# Actuation.net
KiCad netlist of a schematic drawn in Altium Designer
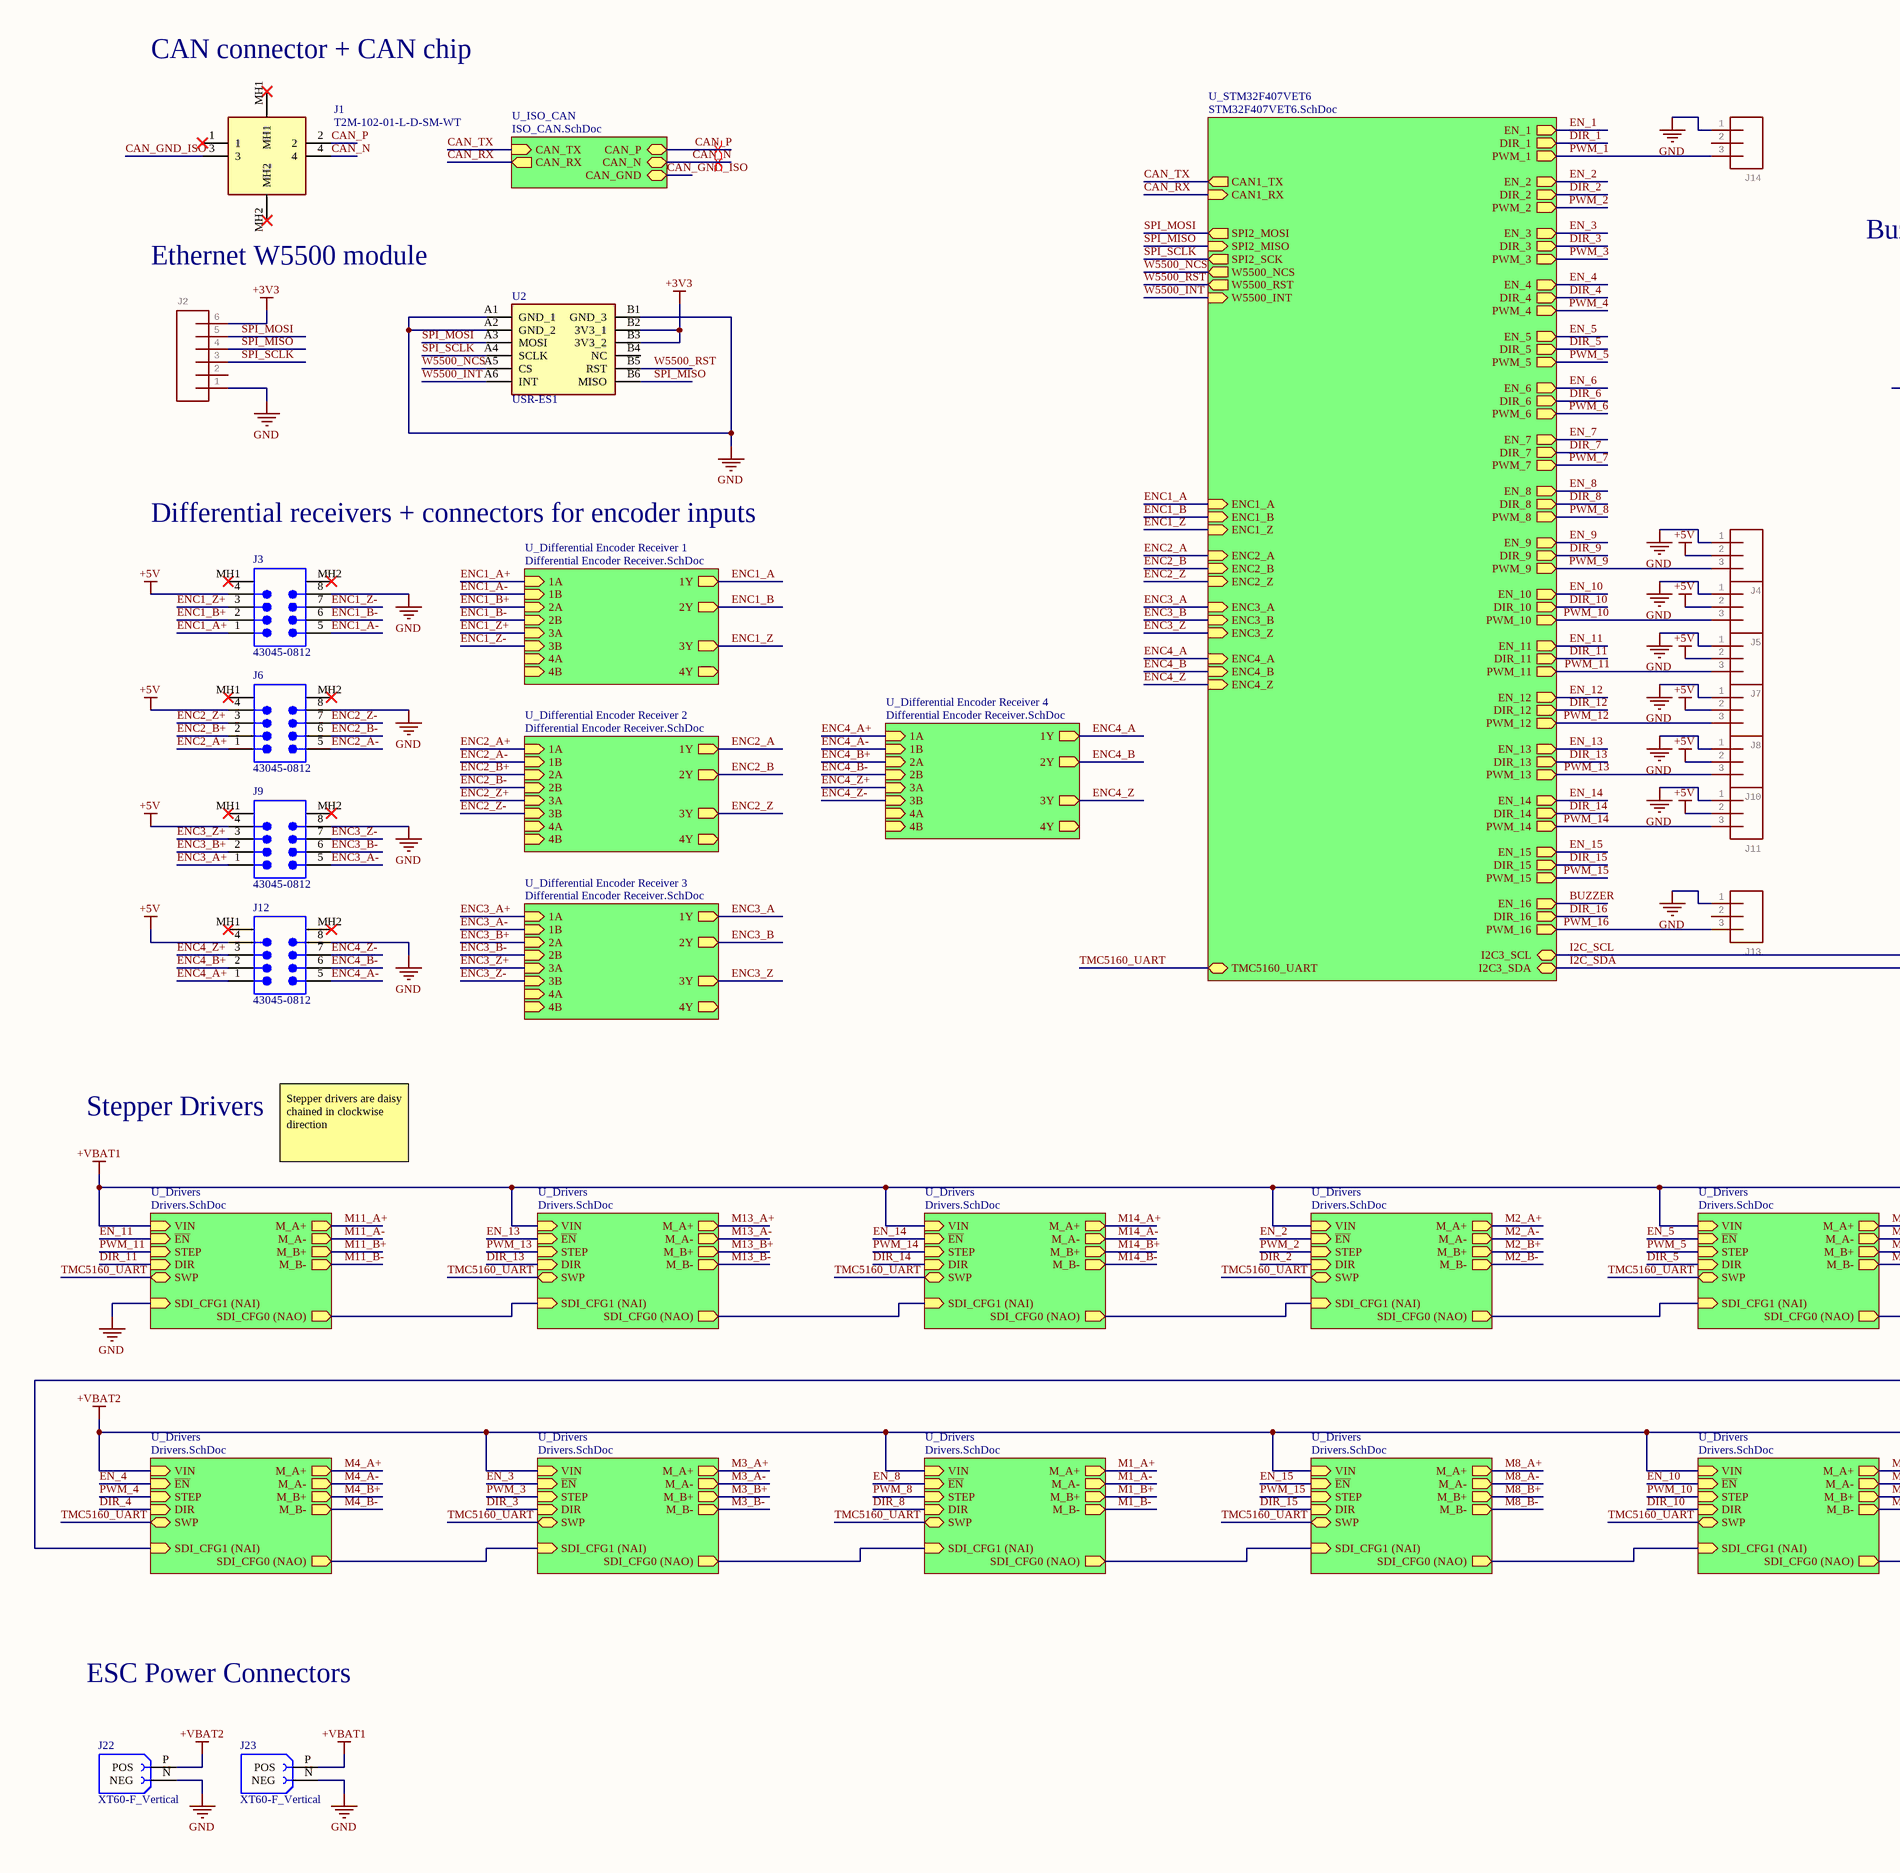
[diagram p0: Actuation.SchDoc, left]
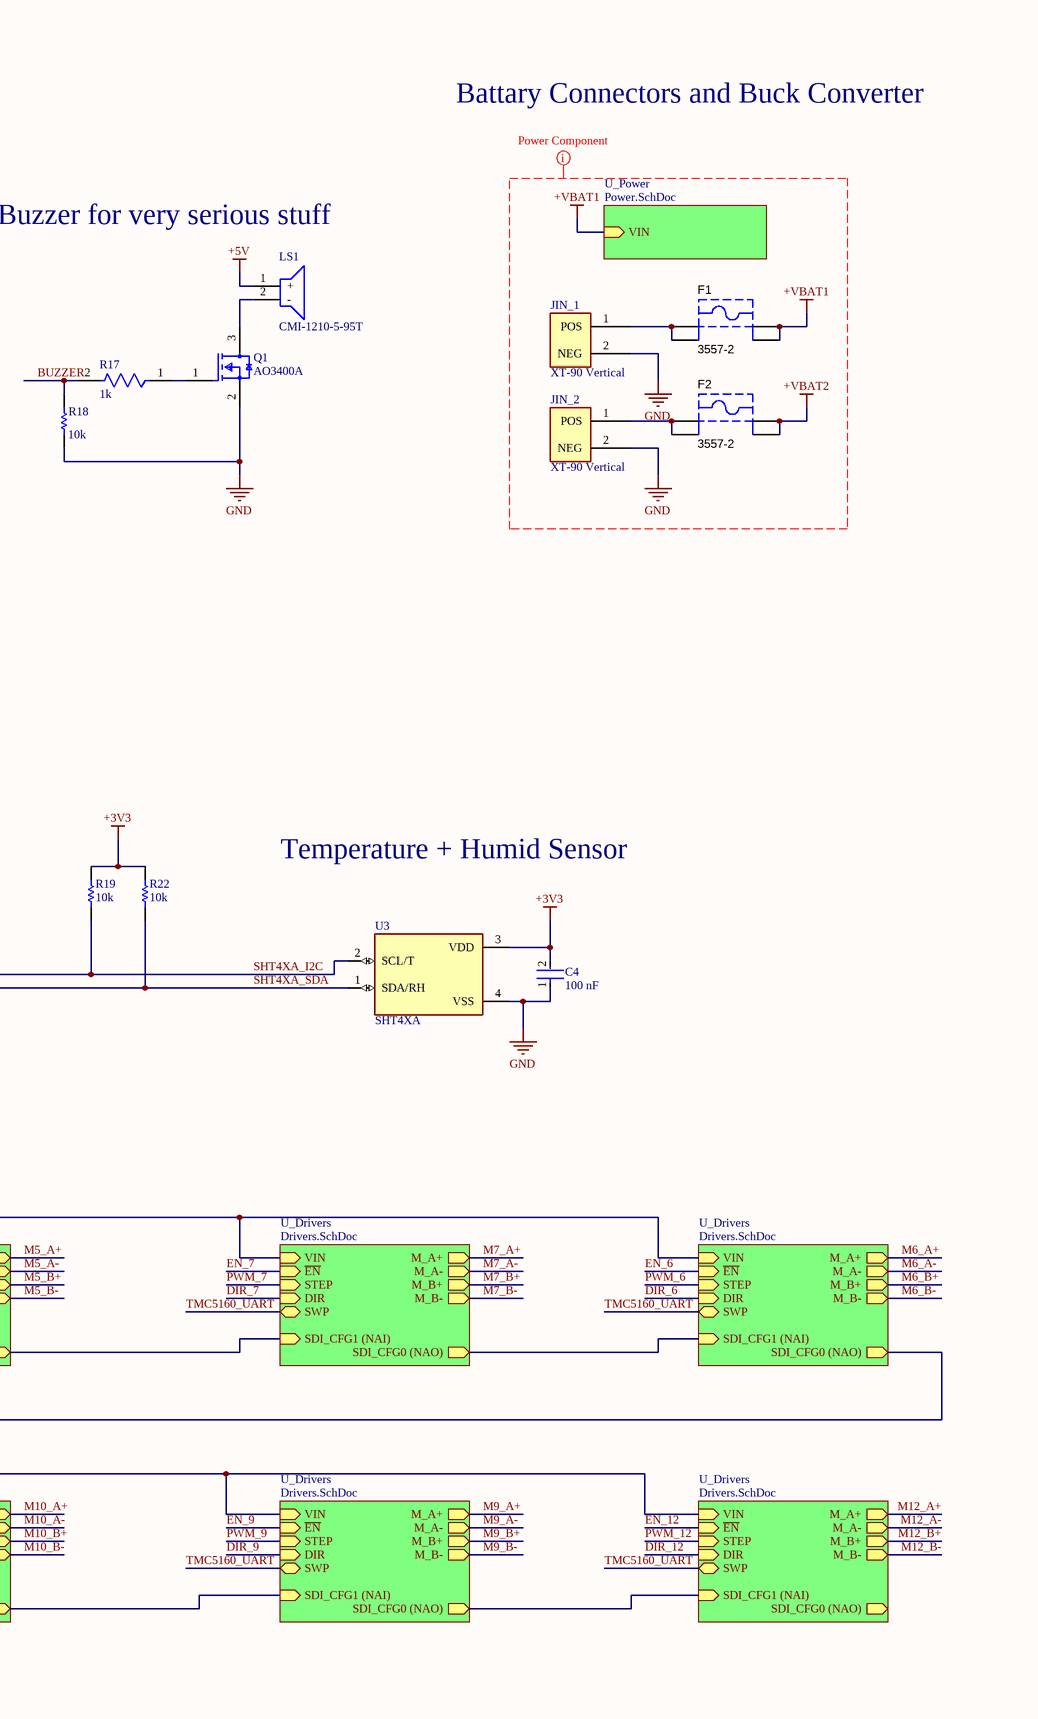
[diagram p1: Actuation.SchDoc, right]

(export (version "E")
  (design (tool "Eeschema 10.0.6"))
  (components
    (comp (ref "C4")
      (value "CC0603KRX7R9BB104")
      (footprint "FP-CC0603-DA-MFG")
      (description "CAP CER 0.1UF 50V X7R 0603")
      (fields
        (field (name "MANUFACTURER") "YAGEO")
        (field (name "VOLTAGE") "50 V")
        (field (name "CAPACITANCE") "100 nF")
      )
      (libsource (lib "Altium Content Vault") (part "11868f565c42a9108669ba33697ecf6"))
    )
    (comp (ref "F1")
      (value "3557-2")
      (footprint "KSTN-3557-2")
      (description "FUSE HOLDER, PCB MOUNT, 500VAC, 20A, ROHS")
      (fields (field (name "VOLTAGE") "500V") (field (name "MANUFACTURER") "Keystone-Electronics"))
      (libsource (lib "Altium Content Vault") (part "FUSE_HOLDER-4"))
    )
    (comp (ref "F2")
      (value "3557-2")
      (footprint "KSTN-3557-2")
      (description "FUSE HOLDER, PCB MOUNT, 500VAC, 20A, ROHS")
      (fields (field (name "VOLTAGE") "500V") (field (name "MANUFACTURER") "Keystone-Electronics"))
      (libsource (lib "Altium Content Vault") (part "FUSE_HOLDER-4"))
    )
    (comp (ref "J1")
      (value "T2M-102-01-L-D-SM-WT")
      (footprint "T2M10201LDSMWT")
      (description "Connector")
      (fields (field (name "MOUSER PART NUMBER") "200-T2M10201LDSMWT"))
      (libsource (lib "BumbleBee Autonomous Systems - NUS") (part "T2M-102-01-L-D-SM-WT"))
    )
    (comp (ref "J2")
      (value "Multi connection point. Often used as Generic Header-pin footprint for 0.1 inch spaced/style header connections    On any of the 0.1 inch spaced packages, you can populate with these:  Break Away Headers - Straight (PRT-00116)   Break Away Male Headers - Right Angle (PRT-00553)   Female Headers (PRT-00115)   Break Away Headers - Machine Pin (PRT-00117)   Break Away Female Headers - Swiss Machine Pin (PRT-00743)   Arduino Stackable Header - 6 Pin (PRT-09280)   Screw Terminals 2.54mm Pitch (6-Pin) (PRT-16499)        For SCREWTERMINALS and SPRING TERMINALS visit here:  Screw Terimnals on SparkFun.com (5mm/3.5mm/2.54mm spacing)       This device is also useful as a general connection point to wire up your design to another part of your project. Our various solder wires solder well into these plated through hole pads.  Hook-Up Wire - Assortment (Stranded, 22 AWG) (PRT-11375)   Hook-Up Wire - Assortment (Solid Core, 22 AWG) (PRT-11367)   View the entire wire category on our website here")
      (footprint "1X06_LOCK")
      (libsource (lib "SparkFun-Connectors.Library") (part "CONN_06LOCK"))
    )
    (comp (ref "J3")
      (value "43045-0812")
      (footprint "MOLX-43045-0812_V")
      (libsource (lib "Altium Content Vault") (part "MOLX-43045-0812"))
    )
    (comp (ref "J4")
      (value "Multi connection point. Often used as Generic Header-pin footprint for 0.1 inch spaced/style header connections    On any of the 0.1 inch spaced packages, you can populate with these:  Break Away Headers - Straight (PRT-00116)   Break Away Male Headers - Right Angle (PRT-00553)   Female Headers (PRT-00115)   Break Away Headers - Machine Pin (PRT-00117)   Break Away Female Headers - Swiss Machine Pin (PRT-00743)   Stackable Header - 3 Pin (Female, 0.1\") (PRT-13875)        For SCREWTERMINALS and SPRING TERMINALS visit here:  Screw Terimnals on SparkFun.com (5mm/3.5mm/2.54mm spacing)       This device is also useful as a general connection point to wire up your design to another part of your project. Our various solder wires solder well into these plated through hole pads.  Hook-Up Wire - Assortment (Stranded, 22 AWG) (PRT-11375)   Hook-Up Wire - Assortment (Solid Core, 22 AWG) (PRT-11367)   View the entire wire category on our website here          Special notes:         Molex polarized connector foot print use with SKU : PRT-08232 with associated crimp pins and housings.")
      (footprint "1X03_LOCK")
      (libsource (lib "SparkFun-Connectors.Library") (part "CONN_03LOCK"))
    )
    (comp (ref "J5")
      (value "Multi connection point. Often used as Generic Header-pin footprint for 0.1 inch spaced/style header connections    On any of the 0.1 inch spaced packages, you can populate with these:  Break Away Headers - Straight (PRT-00116)   Break Away Male Headers - Right Angle (PRT-00553)   Female Headers (PRT-00115)   Break Away Headers - Machine Pin (PRT-00117)   Break Away Female Headers - Swiss Machine Pin (PRT-00743)   Stackable Header - 3 Pin (Female, 0.1\") (PRT-13875)        For SCREWTERMINALS and SPRING TERMINALS visit here:  Screw Terimnals on SparkFun.com (5mm/3.5mm/2.54mm spacing)       This device is also useful as a general connection point to wire up your design to another part of your project. Our various solder wires solder well into these plated through hole pads.  Hook-Up Wire - Assortment (Stranded, 22 AWG) (PRT-11375)   Hook-Up Wire - Assortment (Solid Core, 22 AWG) (PRT-11367)   View the entire wire category on our website here          Special notes:         Molex polarized connector foot print use with SKU : PRT-08232 with associated crimp pins and housings.")
      (footprint "1X03_LOCK")
      (libsource (lib "SparkFun-Connectors.Library") (part "CONN_03LOCK"))
    )
    (comp (ref "J6")
      (value "43045-0812")
      (footprint "MOLX-43045-0812_V")
      (libsource (lib "Altium Content Vault") (part "MOLX-43045-0812"))
    )
    (comp (ref "J7")
      (value "Multi connection point. Often used as Generic Header-pin footprint for 0.1 inch spaced/style header connections    On any of the 0.1 inch spaced packages, you can populate with these:  Break Away Headers - Straight (PRT-00116)   Break Away Male Headers - Right Angle (PRT-00553)   Female Headers (PRT-00115)   Break Away Headers - Machine Pin (PRT-00117)   Break Away Female Headers - Swiss Machine Pin (PRT-00743)   Stackable Header - 3 Pin (Female, 0.1\") (PRT-13875)        For SCREWTERMINALS and SPRING TERMINALS visit here:  Screw Terimnals on SparkFun.com (5mm/3.5mm/2.54mm spacing)       This device is also useful as a general connection point to wire up your design to another part of your project. Our various solder wires solder well into these plated through hole pads.  Hook-Up Wire - Assortment (Stranded, 22 AWG) (PRT-11375)   Hook-Up Wire - Assortment (Solid Core, 22 AWG) (PRT-11367)   View the entire wire category on our website here          Special notes:         Molex polarized connector foot print use with SKU : PRT-08232 with associated crimp pins and housings.")
      (footprint "1X03_LOCK")
      (libsource (lib "SparkFun-Connectors.Library") (part "CONN_03LOCK"))
    )
    (comp (ref "J8")
      (value "Multi connection point. Often used as Generic Header-pin footprint for 0.1 inch spaced/style header connections    On any of the 0.1 inch spaced packages, you can populate with these:  Break Away Headers - Straight (PRT-00116)   Break Away Male Headers - Right Angle (PRT-00553)   Female Headers (PRT-00115)   Break Away Headers - Machine Pin (PRT-00117)   Break Away Female Headers - Swiss Machine Pin (PRT-00743)   Stackable Header - 3 Pin (Female, 0.1\") (PRT-13875)        For SCREWTERMINALS and SPRING TERMINALS visit here:  Screw Terimnals on SparkFun.com (5mm/3.5mm/2.54mm spacing)       This device is also useful as a general connection point to wire up your design to another part of your project. Our various solder wires solder well into these plated through hole pads.  Hook-Up Wire - Assortment (Stranded, 22 AWG) (PRT-11375)   Hook-Up Wire - Assortment (Solid Core, 22 AWG) (PRT-11367)   View the entire wire category on our website here          Special notes:         Molex polarized connector foot print use with SKU : PRT-08232 with associated crimp pins and housings.")
      (footprint "1X03_LOCK")
      (libsource (lib "SparkFun-Connectors.Library") (part "CONN_03LOCK"))
    )
    (comp (ref "J9")
      (value "43045-0812")
      (footprint "MOLX-43045-0812_V")
      (libsource (lib "Altium Content Vault") (part "MOLX-43045-0812"))
    )
    (comp (ref "J10")
      (value "Multi connection point. Often used as Generic Header-pin footprint for 0.1 inch spaced/style header connections    On any of the 0.1 inch spaced packages, you can populate with these:  Break Away Headers - Straight (PRT-00116)   Break Away Male Headers - Right Angle (PRT-00553)   Female Headers (PRT-00115)   Break Away Headers - Machine Pin (PRT-00117)   Break Away Female Headers - Swiss Machine Pin (PRT-00743)   Stackable Header - 3 Pin (Female, 0.1\") (PRT-13875)        For SCREWTERMINALS and SPRING TERMINALS visit here:  Screw Terimnals on SparkFun.com (5mm/3.5mm/2.54mm spacing)       This device is also useful as a general connection point to wire up your design to another part of your project. Our various solder wires solder well into these plated through hole pads.  Hook-Up Wire - Assortment (Stranded, 22 AWG) (PRT-11375)   Hook-Up Wire - Assortment (Solid Core, 22 AWG) (PRT-11367)   View the entire wire category on our website here          Special notes:         Molex polarized connector foot print use with SKU : PRT-08232 with associated crimp pins and housings.")
      (footprint "1X03_LOCK")
      (libsource (lib "SparkFun-Connectors.Library") (part "CONN_03LOCK"))
    )
    (comp (ref "J11")
      (value "Multi connection point. Often used as Generic Header-pin footprint for 0.1 inch spaced/style header connections    On any of the 0.1 inch spaced packages, you can populate with these:  Break Away Headers - Straight (PRT-00116)   Break Away Male Headers - Right Angle (PRT-00553)   Female Headers (PRT-00115)   Break Away Headers - Machine Pin (PRT-00117)   Break Away Female Headers - Swiss Machine Pin (PRT-00743)   Stackable Header - 3 Pin (Female, 0.1\") (PRT-13875)        For SCREWTERMINALS and SPRING TERMINALS visit here:  Screw Terimnals on SparkFun.com (5mm/3.5mm/2.54mm spacing)       This device is also useful as a general connection point to wire up your design to another part of your project. Our various solder wires solder well into these plated through hole pads.  Hook-Up Wire - Assortment (Stranded, 22 AWG) (PRT-11375)   Hook-Up Wire - Assortment (Solid Core, 22 AWG) (PRT-11367)   View the entire wire category on our website here          Special notes:         Molex polarized connector foot print use with SKU : PRT-08232 with associated crimp pins and housings.")
      (footprint "1X03_LOCK")
      (libsource (lib "SparkFun-Connectors.Library") (part "CONN_03LOCK"))
    )
    (comp (ref "J12")
      (value "43045-0812")
      (footprint "MOLX-43045-0812_V")
      (libsource (lib "Altium Content Vault") (part "MOLX-43045-0812"))
    )
    (comp (ref "J13")
      (value "Multi connection point. Often used as Generic Header-pin footprint for 0.1 inch spaced/style header connections    On any of the 0.1 inch spaced packages, you can populate with these:  Break Away Headers - Straight (PRT-00116)   Break Away Male Headers - Right Angle (PRT-00553)   Female Headers (PRT-00115)   Break Away Headers - Machine Pin (PRT-00117)   Break Away Female Headers - Swiss Machine Pin (PRT-00743)   Stackable Header - 3 Pin (Female, 0.1\") (PRT-13875)        For SCREWTERMINALS and SPRING TERMINALS visit here:  Screw Terimnals on SparkFun.com (5mm/3.5mm/2.54mm spacing)       This device is also useful as a general connection point to wire up your design to another part of your project. Our various solder wires solder well into these plated through hole pads.  Hook-Up Wire - Assortment (Stranded, 22 AWG) (PRT-11375)   Hook-Up Wire - Assortment (Solid Core, 22 AWG) (PRT-11367)   View the entire wire category on our website here          Special notes:         Molex polarized connector foot print use with SKU : PRT-08232 with associated crimp pins and housings.")
      (footprint "1X03_LOCK")
      (libsource (lib "SparkFun-Connectors.Library") (part "CONN_03LOCK"))
    )
    (comp (ref "J14")
      (value "Multi connection point. Often used as Generic Header-pin footprint for 0.1 inch spaced/style header connections    On any of the 0.1 inch spaced packages, you can populate with these:  Break Away Headers - Straight (PRT-00116)   Break Away Male Headers - Right Angle (PRT-00553)   Female Headers (PRT-00115)   Break Away Headers - Machine Pin (PRT-00117)   Break Away Female Headers - Swiss Machine Pin (PRT-00743)   Stackable Header - 3 Pin (Female, 0.1\") (PRT-13875)        For SCREWTERMINALS and SPRING TERMINALS visit here:  Screw Terimnals on SparkFun.com (5mm/3.5mm/2.54mm spacing)       This device is also useful as a general connection point to wire up your design to another part of your project. Our various solder wires solder well into these plated through hole pads.  Hook-Up Wire - Assortment (Stranded, 22 AWG) (PRT-11375)   Hook-Up Wire - Assortment (Solid Core, 22 AWG) (PRT-11367)   View the entire wire category on our website here          Special notes:         Molex polarized connector foot print use with SKU : PRT-08232 with associated crimp pins and housings.")
      (footprint "1X03_LOCK")
      (libsource (lib "SparkFun-Connectors.Library") (part "CONN_03LOCK"))
    )
    (comp (ref "J22")
      (value "XT60-F_Vertical")
      (footprint "AMASS_XT60-F_1x02_P7.20mm_Vertical")
      (libsource (lib "BumbleBee Autonomous Systems - NUS") (part "XT90PW-F"))
    )
    (comp (ref "J23")
      (value "XT60-F_Vertical")
      (footprint "AMASS_XT60-F_1x02_P7.20mm_Vertical")
      (libsource (lib "BumbleBee Autonomous Systems - NUS") (part "XT90PW-F"))
    )
    (comp (ref "JIN_1")
      (value "XT-90 Vertical")
      (footprint "XT-90 Vertical-Footprint-1")
      (libsource (lib "BumbleBee Autonomous Systems - NUS") (part "XT90 Vertical"))
    )
    (comp (ref "JIN_2")
      (value "XT-90 Vertical")
      (footprint "XT-90 Vertical-Footprint-1")
      (libsource (lib "BumbleBee Autonomous Systems - NUS") (part "XT90 Vertical"))
    )
    (comp (ref "LS1")
      (value "CMI-1210-5-95T")
      (footprint "SamacSys:CMI1210595T")
      (description "Loudspeaker or Buzzer")
      (fields (field (name "MOUSER PART NUMBER") "179-CMI-1210-5-95T"))
      (libsource (lib "*") (part "CMI-1210-5-95T"))
    )
    (comp (ref "Q1")
      (value "AO3400A")
      (footprint "FP-SOT23-MFG")
      (description "MOSFET N-CH 30V 5.7A SOT23")
      (libsource (lib "Altium Content Vault") (part "0a9ea7c96deaaede766a5b531c28de0"))
    )
    (comp (ref "R17")
      (value "1k")
      (footprint "FP-RC0603-0_55-IPC_C")
      (description "RC0603FR-071KL. RES 1K OHM 1% 1/10W 0603")
      (fields (field (name "TOLERANCE") "1%"))
      (libsource (lib "Altium Content Vault") (part "1029c3af85768c4190bb7ad29bc67b5"))
    )
    (comp (ref "R18")
      (value "0603WAF1002T5E")
      (footprint "RESC1609X50X30NL8T20")
      (description "100mW Thick Film Resistors 75V ±100ppm/℃ ±1% 10kΩ 0603 Chip Resistor - Surface Mount ROHS")
      (fields (field (name "RESISTANCE") "10k"))
      (libsource (lib "Altium Content Vault") (part "RES-2"))
    )
    (comp (ref "R19")
      (value "0603WAF1002T5E")
      (footprint "RESC1609X50X30NL8T20")
      (description "100mW Thick Film Resistors 75V ±100ppm/℃ ±1% 10kΩ 0603 Chip Resistor - Surface Mount ROHS")
      (fields (field (name "RESISTANCE") "10k"))
      (libsource (lib "Altium Content Vault") (part "RES-2"))
    )
    (comp (ref "R22")
      (value "0603WAF1002T5E")
      (footprint "RESC1609X50X30NL8T20")
      (description "100mW Thick Film Resistors 75V ±100ppm/℃ ±1% 10kΩ 0603 Chip Resistor - Surface Mount ROHS")
      (fields (field (name "RESISTANCE") "10k"))
      (libsource (lib "Altium Content Vault") (part "RES-2"))
    )
    (comp (ref "U2")
      (value "USR-ES1")
      (footprint "USRES1")
      (description "Integrated Circuit")
      (libsource (lib "BumbleBee Autonomous Systems - NUS") (part "USR-ES1"))
    )
    (comp (ref "U3")
      (value "SHT4XA")
      (footprint "SHT4XA")
      (description "Automotive Grade Relative Humidity Temperature Sensor, Â±3 %RH, Â±0.3 Â°C")
      (fields (field (name "MF") "Sensirion") (field (name "MP") "SHT40A-AD1B-R3"))
      (libsource (lib "BumbleBee Autonomous Systems - NUS") (part "SHT4XA"))
    )
  )
  (nets
    (net (code "1") (name "+3V3") (class "Default")
      (node (ref "C4") (pin "2") (pinfunction "2_2") (pintype "passive"))
      (node (ref "J2") (pin "6") (pinfunction "6_6") (pintype "passive"))
      (node (ref "R19") (pin "2") (pinfunction "2_2") (pintype "passive"))
      (node (ref "R22") (pin "2") (pinfunction "2_2") (pintype "passive"))
      (node (ref "U2") (pin "B2") (pinfunction "3V3_1_B2") (pintype "passive"))
      (node (ref "U2") (pin "B3") (pinfunction "3V3_2_B3") (pintype "passive"))
      (node (ref "U3") (pin "3") (pinfunction "VDD_3") (pintype "power_in"))
    )
    (net (code "2") (name "+5V") (class "Default")
      (node (ref "J10") (pin "2") (pinfunction "2_2") (pintype "passive"))
      (node (ref "J11") (pin "2") (pinfunction "2_2") (pintype "passive"))
      (node (ref "J12") (pin "4") (pinfunction "4_4") (pintype "passive"))
      (node (ref "J3") (pin "4") (pinfunction "4_4") (pintype "passive"))
      (node (ref "J4") (pin "2") (pinfunction "2_2") (pintype "passive"))
      (node (ref "J5") (pin "2") (pinfunction "2_2") (pintype "passive"))
      (node (ref "J6") (pin "4") (pinfunction "4_4") (pintype "passive"))
      (node (ref "J7") (pin "2") (pinfunction "2_2") (pintype "passive"))
      (node (ref "J8") (pin "2") (pinfunction "2_2") (pintype "passive"))
      (node (ref "J9") (pin "4") (pinfunction "4_4") (pintype "passive"))
      (node (ref "LS1") (pin "1") (pinfunction "+_1") (pintype "passive"))
    )
    (net (code "3") (name "+VBAT1") (class "Default")
      (node (ref "F1") (pin "3") (pinfunction "3_3") (pintype "passive"))
      (node (ref "F1") (pin "4") (pinfunction "4_4") (pintype "passive"))
      (node (ref "J23") (pin "P") (pinfunction "POS_P") (pintype "passive"))
    )
    (net (code "4") (name "+VBAT2") (class "Default")
      (node (ref "F2") (pin "3") (pinfunction "3_3") (pintype "passive"))
      (node (ref "F2") (pin "4") (pinfunction "4_4") (pintype "passive"))
      (node (ref "J22") (pin "P") (pinfunction "POS_P") (pintype "passive"))
    )
    (net (code "17") (name "/BUZZER") (class "Default")
      (node (ref "R17") (pin "2") (pinfunction "2_2") (pintype "passive"))
      (node (ref "R18") (pin "1") (pinfunction "1_1") (pintype "passive"))
    )
    (net (code "18") (name "/CAN_GND_ISO") (class "Default")
      (node (ref "J1") (pin "3") (pinfunction "3_3") (pintype "passive"))
    )
    (net (code "19") (name "/CAN_N") (class "Default")
      (node (ref "J1") (pin "4") (pinfunction "4_4") (pintype "passive"))
    )
    (net (code "20") (name "/CAN_P") (class "Default")
      (node (ref "J1") (pin "2") (pinfunction "2_2") (pintype "passive"))
    )
    (net (code "40") (name "/ENC1_A+") (class "Default")
      (node (ref "J3") (pin "1") (pinfunction "1_1") (pintype "passive"))
    )
    (net (code "41") (name "/ENC1_A-") (class "Default")
      (node (ref "J3") (pin "5") (pinfunction "5_5") (pintype "passive"))
    )
    (net (code "43") (name "/ENC1_B+") (class "Default")
      (node (ref "J3") (pin "2") (pinfunction "2_2") (pintype "passive"))
    )
    (net (code "44") (name "/ENC1_B-") (class "Default")
      (node (ref "J3") (pin "6") (pinfunction "6_6") (pintype "passive"))
    )
    (net (code "46") (name "/ENC1_Z+") (class "Default")
      (node (ref "J3") (pin "3") (pinfunction "3_3") (pintype "passive"))
    )
    (net (code "47") (name "/ENC1_Z-") (class "Default")
      (node (ref "J3") (pin "7") (pinfunction "7_7") (pintype "passive"))
    )
    (net (code "49") (name "/ENC2_A+") (class "Default")
      (node (ref "J6") (pin "1") (pinfunction "1_1") (pintype "passive"))
    )
    (net (code "50") (name "/ENC2_A-") (class "Default")
      (node (ref "J6") (pin "5") (pinfunction "5_5") (pintype "passive"))
    )
    (net (code "52") (name "/ENC2_B+") (class "Default")
      (node (ref "J6") (pin "2") (pinfunction "2_2") (pintype "passive"))
    )
    (net (code "53") (name "/ENC2_B-") (class "Default")
      (node (ref "J6") (pin "6") (pinfunction "6_6") (pintype "passive"))
    )
    (net (code "55") (name "/ENC2_Z+") (class "Default")
      (node (ref "J6") (pin "3") (pinfunction "3_3") (pintype "passive"))
    )
    (net (code "56") (name "/ENC2_Z-") (class "Default")
      (node (ref "J6") (pin "7") (pinfunction "7_7") (pintype "passive"))
    )
    (net (code "58") (name "/ENC3_A+") (class "Default")
      (node (ref "J9") (pin "1") (pinfunction "1_1") (pintype "passive"))
    )
    (net (code "59") (name "/ENC3_A-") (class "Default")
      (node (ref "J9") (pin "5") (pinfunction "5_5") (pintype "passive"))
    )
    (net (code "61") (name "/ENC3_B+") (class "Default")
      (node (ref "J9") (pin "2") (pinfunction "2_2") (pintype "passive"))
    )
    (net (code "62") (name "/ENC3_B-") (class "Default")
      (node (ref "J9") (pin "6") (pinfunction "6_6") (pintype "passive"))
    )
    (net (code "64") (name "/ENC3_Z+") (class "Default")
      (node (ref "J9") (pin "3") (pinfunction "3_3") (pintype "passive"))
    )
    (net (code "65") (name "/ENC3_Z-") (class "Default")
      (node (ref "J9") (pin "7") (pinfunction "7_7") (pintype "passive"))
    )
    (net (code "67") (name "/ENC4_A+") (class "Default")
      (node (ref "J12") (pin "1") (pinfunction "1_1") (pintype "passive"))
    )
    (net (code "68") (name "/ENC4_A-") (class "Default")
      (node (ref "J12") (pin "5") (pinfunction "5_5") (pintype "passive"))
    )
    (net (code "70") (name "/ENC4_B+") (class "Default")
      (node (ref "J12") (pin "2") (pinfunction "2_2") (pintype "passive"))
    )
    (net (code "71") (name "/ENC4_B-") (class "Default")
      (node (ref "J12") (pin "6") (pinfunction "6_6") (pintype "passive"))
    )
    (net (code "73") (name "/ENC4_Z+") (class "Default")
      (node (ref "J12") (pin "3") (pinfunction "3_3") (pintype "passive"))
    )
    (net (code "74") (name "/ENC4_Z-") (class "Default")
      (node (ref "J12") (pin "7") (pinfunction "7_7") (pintype "passive"))
    )
    (net (code "90") (name "/I2C_SCL") (class "Default")
      (node (ref "R19") (pin "1") (pinfunction "1_1") (pintype "passive"))
      (node (ref "U3") (pin "2") (pinfunction "SCL/T_2") (pintype "bidirectional"))
    )
    (net (code "91") (name "/I2C_SDA") (class "Default")
      (node (ref "R22") (pin "1") (pinfunction "1_1") (pintype "passive"))
      (node (ref "U3") (pin "1") (pinfunction "SDA/RH_1") (pintype "bidirectional"))
    )
    (net (code "148") (name "/PWM_1") (class "Default")
      (node (ref "J14") (pin "3") (pinfunction "3_3") (pintype "passive"))
    )
    (net (code "156") (name "/PWM_9") (class "Default")
      (node (ref "J4") (pin "3") (pinfunction "3_3") (pintype "passive"))
    )
    (net (code "157") (name "/PWM_10") (class "Default")
      (node (ref "J5") (pin "3") (pinfunction "3_3") (pintype "passive"))
    )
    (net (code "158") (name "/PWM_11") (class "Default")
      (node (ref "J7") (pin "3") (pinfunction "3_3") (pintype "passive"))
    )
    (net (code "159") (name "/PWM_12") (class "Default")
      (node (ref "J8") (pin "3") (pinfunction "3_3") (pintype "passive"))
    )
    (net (code "160") (name "/PWM_13") (class "Default")
      (node (ref "J10") (pin "3") (pinfunction "3_3") (pintype "passive"))
    )
    (net (code "161") (name "/PWM_14") (class "Default")
      (node (ref "J11") (pin "3") (pinfunction "3_3") (pintype "passive"))
    )
    (net (code "163") (name "/PWM_16") (class "Default")
      (node (ref "J13") (pin "3") (pinfunction "3_3") (pintype "passive"))
    )
    (net (code "178") (name "/SPI_MISO") (class "Default")
      (node (ref "J2") (pin "4") (pinfunction "4_4") (pintype "passive"))
      (node (ref "U2") (pin "B6") (pinfunction "MISO_B6") (pintype "passive"))
    )
    (net (code "179") (name "/SPI_MOSI") (class "Default")
      (node (ref "J2") (pin "5") (pinfunction "5_5") (pintype "passive"))
      (node (ref "U2") (pin "A3") (pinfunction "MOSI_A3") (pintype "passive"))
    )
    (net (code "180") (name "/SPI_SCLK") (class "Default")
      (node (ref "J2") (pin "3") (pinfunction "3_3") (pintype "passive"))
      (node (ref "U2") (pin "A4") (pinfunction "SCLK_A4") (pintype "passive"))
    )
    (net (code "182") (name "/W5500_INT") (class "Default")
      (node (ref "U2") (pin "A6") (pinfunction "INT_A6") (pintype "passive"))
    )
    (net (code "183") (name "/W5500_NCS") (class "Default")
      (node (ref "U2") (pin "A5") (pinfunction "CS_A5") (pintype "passive"))
    )
    (net (code "184") (name "/W5500_RST") (class "Default")
      (node (ref "U2") (pin "B5") (pinfunction "RST_B5") (pintype "passive"))
    )
    (net (code "185") (name "GND") (class "Default")
      (node (ref "C4") (pin "1") (pinfunction "1_1") (pintype "passive"))
      (node (ref "J10") (pin "1") (pinfunction "1_1") (pintype "passive"))
      (node (ref "J11") (pin "1") (pinfunction "1_1") (pintype "passive"))
      (node (ref "J12") (pin "8") (pinfunction "8_8") (pintype "passive"))
      (node (ref "J13") (pin "1") (pinfunction "1_1") (pintype "passive"))
      (node (ref "J14") (pin "1") (pinfunction "1_1") (pintype "passive"))
      (node (ref "J2") (pin "1") (pinfunction "1_1") (pintype "passive"))
      (node (ref "J22") (pin "N") (pinfunction "NEG_N") (pintype "passive"))
      (node (ref "J23") (pin "N") (pinfunction "NEG_N") (pintype "passive"))
      (node (ref "J3") (pin "8") (pinfunction "8_8") (pintype "passive"))
      (node (ref "J4") (pin "1") (pinfunction "1_1") (pintype "passive"))
      (node (ref "J5") (pin "1") (pinfunction "1_1") (pintype "passive"))
      (node (ref "J6") (pin "8") (pinfunction "8_8") (pintype "passive"))
      (node (ref "J7") (pin "1") (pinfunction "1_1") (pintype "passive"))
      (node (ref "J8") (pin "1") (pinfunction "1_1") (pintype "passive"))
      (node (ref "J9") (pin "8") (pinfunction "8_8") (pintype "passive"))
      (node (ref "JIN_1") (pin "2") (pinfunction "NEG_2") (pintype "power_in"))
      (node (ref "JIN_2") (pin "2") (pinfunction "NEG_2") (pintype "power_in"))
      (node (ref "Q1") (pin "2") (pinfunction "S_2") (pintype "passive"))
      (node (ref "R18") (pin "2") (pinfunction "2_2") (pintype "passive"))
      (node (ref "U2") (pin "A1") (pinfunction "GND_1_A1") (pintype "passive"))
      (node (ref "U2") (pin "A2") (pinfunction "GND_2_A2") (pintype "passive"))
      (node (ref "U2") (pin "B1") (pinfunction "GND_3_B1") (pintype "passive"))
      (node (ref "U3") (pin "4") (pinfunction "VSS_4") (pintype "power_in"))
    )
    (net (code "186") (name "Net-(JIN_1-POS)") (class "Default")
      (node (ref "F1") (pin "1") (pinfunction "1_1") (pintype "passive"))
      (node (ref "F1") (pin "2") (pinfunction "2_2") (pintype "passive"))
      (node (ref "JIN_1") (pin "1") (pinfunction "POS_1") (pintype "power_in"))
    )
    (net (code "187") (name "Net-(JIN_2-POS)") (class "Default")
      (node (ref "F2") (pin "1") (pinfunction "1_1") (pintype "passive"))
      (node (ref "F2") (pin "2") (pinfunction "2_2") (pintype "passive"))
      (node (ref "JIN_2") (pin "1") (pinfunction "POS_1") (pintype "power_in"))
    )
    (net (code "188") (name "Net-(LS1--)") (class "Default")
      (node (ref "LS1") (pin "2") (pinfunction "-_2") (pintype "passive"))
      (node (ref "Q1") (pin "3") (pinfunction "D_3") (pintype "passive"))
    )
    (net (code "189") (name "Net-(Q1-G)") (class "Default")
      (node (ref "Q1") (pin "1") (pinfunction "G_1") (pintype "passive"))
      (node (ref "R17") (pin "1") (pinfunction "1_1") (pintype "passive"))
    )
    (net (code "190") (name "unconnected-(J1-Pad1)") (class "Default")
      (node (ref "J1") (pin "1") (pinfunction "1_1") (pintype "passive+no_connect"))
    )
    (net (code "191") (name "unconnected-(J1-PadMH1)") (class "Default")
      (node (ref "J1") (pin "MH1") (pinfunction "MH1_MH1") (pintype "passive+no_connect"))
    )
    (net (code "192") (name "unconnected-(J1-PadMH2)") (class "Default")
      (node (ref "J1") (pin "MH2") (pinfunction "MH2_MH2") (pintype "passive+no_connect"))
    )
    (net (code "193") (name "unconnected-(J2-Pad2)") (class "Default")
      (node (ref "J2") (pin "2") (pinfunction "2_2") (pintype "passive"))
    )
    (net (code "194") (name "unconnected-(J3-PadMH1)") (class "Default")
      (node (ref "J3") (pin "MH1") (pinfunction "MH1_MH1") (pintype "passive+no_connect"))
    )
    (net (code "195") (name "unconnected-(J3-PadMH2)") (class "Default")
      (node (ref "J3") (pin "MH2") (pinfunction "MH2_MH2") (pintype "passive+no_connect"))
    )
    (net (code "196") (name "unconnected-(J6-PadMH1)") (class "Default")
      (node (ref "J6") (pin "MH1") (pinfunction "MH1_MH1") (pintype "passive+no_connect"))
    )
    (net (code "197") (name "unconnected-(J6-PadMH2)") (class "Default")
      (node (ref "J6") (pin "MH2") (pinfunction "MH2_MH2") (pintype "passive+no_connect"))
    )
    (net (code "198") (name "unconnected-(J9-PadMH1)") (class "Default")
      (node (ref "J9") (pin "MH1") (pinfunction "MH1_MH1") (pintype "passive+no_connect"))
    )
    (net (code "199") (name "unconnected-(J9-PadMH2)") (class "Default")
      (node (ref "J9") (pin "MH2") (pinfunction "MH2_MH2") (pintype "passive+no_connect"))
    )
    (net (code "200") (name "unconnected-(J12-PadMH1)") (class "Default")
      (node (ref "J12") (pin "MH1") (pinfunction "MH1_MH1") (pintype "passive+no_connect"))
    )
    (net (code "201") (name "unconnected-(J12-PadMH2)") (class "Default")
      (node (ref "J12") (pin "MH2") (pinfunction "MH2_MH2") (pintype "passive+no_connect"))
    )
    (net (code "202") (name "unconnected-(J13-Pad2)") (class "Default")
      (node (ref "J13") (pin "2") (pinfunction "2_2") (pintype "passive"))
    )
    (net (code "203") (name "unconnected-(J14-Pad2)") (class "Default")
      (node (ref "J14") (pin "2") (pinfunction "2_2") (pintype "passive"))
    )
    (net (code "204") (name "unconnected-(U2-NC-PadB4)") (class "Default")
      (node (ref "U2") (pin "B4") (pinfunction "NC_B4") (pintype "passive"))
    )
  )
)
